# station_meteo.net
KiCad netlist of a schematic drawn in EasyEDA Pro
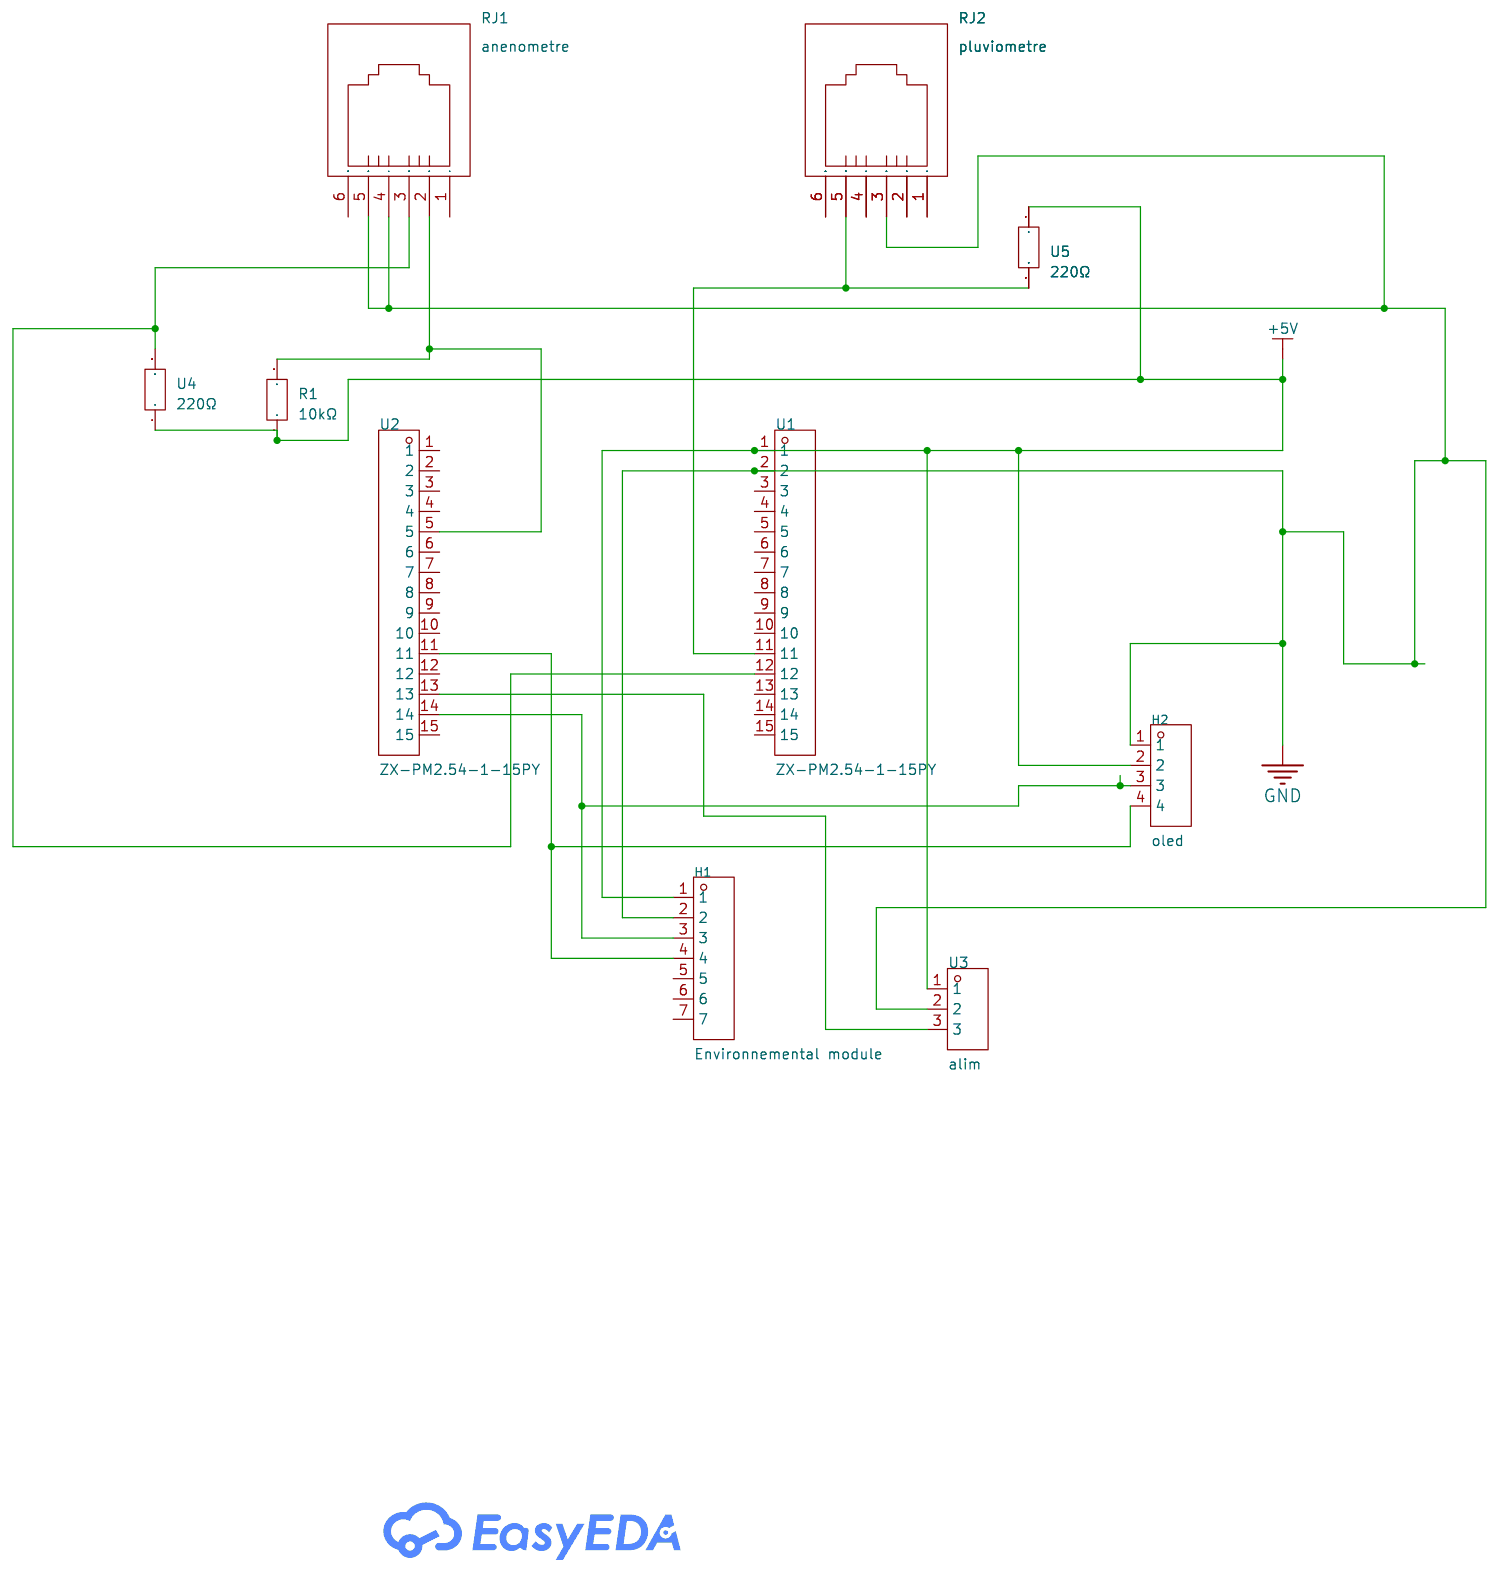
[diagram p0: schematic sheet]

(export (version "E")
  (design (tool "Eeschema 10.0.6"))
  (components
    (comp (ref "H1")
      (value "Environnemental module")
      (footprint "easyedapro:HDR-TH_7P-P2.54-V-F")
      (fields (field (name "Manufacturer") "XFCN(兴飞)"))
      (libsource (lib "easyedapro") (part "PM254V-11-07-H85"))
    )
    (comp (ref "H2")
      (value "oled")
      (footprint "easyedapro:HDR-TH_4P-P2.54-V-F")
      (fields (field (name "Manufacturer") "BOOMELE(博穆精密)"))
      (libsource (lib "easyedapro") (part "2.54-1*4P母"))
    )
    (comp (ref "R1")
      (value "10kΩ")
      (footprint "easyedapro:RES-TH_BD2.7-L6.2-P10.20-D0.4")
      (fields (field (name "Manufacturer Part") "MF1/4W-10K±1%-ST52") (field (name "Manufacturer") "VO(翔胜)"))
      (libsource (lib "easyedapro") (part "MF1/4W-10K±1%-ST52"))
    )
    (comp (ref "RJ1")
      (value "anenometre")
      (footprint "easyedapro:RJ11-TH_DS1133-S60BPX")
      (description "Connector Type:RJ12 Jack Number of Ports:1 LED:- Shielding:- Ratings:-")
      (fields (field (name "Manufacturer") "CONNFLY"))
      (libsource (lib "easyedapro") (part "DS1133-S60BPX"))
    )
    (comp (ref "RJ2")
      (value "pluviometre")
      (footprint "easyedapro:RJ11-TH_DS1133-S60BPX")
      (description "Connector Type:RJ12 Jack Number of Ports:1 LED:- Shielding:- Ratings:-")
      (fields (field (name "Manufacturer") "CONNFLY"))
      (libsource (lib "easyedapro") (part "DS1133-S60BPX"))
    )
    (comp (ref "U1")
      (value "ZX-PM2.54-1-15PY")
      (footprint "easyedapro:HDR-TH_15P-P2.54-V-F")
      (fields (field (name "Manufacturer") "Megastar(兆星)"))
      (libsource (lib "easyedapro") (part "ZX-PM2.54-1-15PY"))
    )
    (comp (ref "U2")
      (value "ZX-PM2.54-1-15PY")
      (footprint "easyedapro:HDR-TH_15P-P2.54-V-F")
      (fields (field (name "Manufacturer") "Megastar(兆星)"))
      (libsource (lib "easyedapro") (part "ZX-PM2.54-1-15PY"))
    )
    (comp (ref "U3")
      (value "alim")
      (footprint "easyedapro:CONN-TH_3P-P5.08_DB128L-5.08-3P-BK-S")
      (fields (field (name "Manufacturer") "DORABO(地博电气)"))
      (libsource (lib "easyedapro") (part "DB128L-5.08-3P-BK-S"))
    )
    (comp (ref "U4")
      (value "220Ω")
      (footprint "easyedapro:RES-TH_BD2.4-L6.3-P10.30-D0.6")
      (fields (field (name "Manufacturer Part") "MFR-25FBF52-220R") (field (name "Manufacturer") "YAGEO(国巨)"))
      (libsource (lib "easyedapro") (part "MFR-25FBF52-220R"))
    )
    (comp (ref "U5")
      (value "220Ω")
      (footprint "easyedapro:RES-TH_BD2.4-L6.3-P10.30-D0.6")
      (fields (field (name "Manufacturer Part") "MFR-25FBF52-220R") (field (name "Manufacturer") "YAGEO(国巨)"))
      (libsource (lib "easyedapro") (part "MFR-25FBF52-220R"))
    )
  )
  (nets
    (net (code "1") (name "+5V") (class "Default")
      (node (ref "H1") (pin "1") (pinfunction "1_1") (pintype "input"))
      (node (ref "H2") (pin "2") (pinfunction "2_2") (pintype "input"))
      (node (ref "R1") (pin "1") (pinfunction "1_1") (pintype "unspecified"))
      (node (ref "U1") (pin "1") (pinfunction "1_1") (pintype "unspecified"))
      (node (ref "U3") (pin "1") (pinfunction "1_1") (pintype "unspecified"))
      (node (ref "U4") (pin "1") (pinfunction "1_1") (pintype "unspecified"))
      (node (ref "U5") (pin "1") (pinfunction "1_1") (pintype "unspecified"))
    )
    (net (code "2") (name "GND") (class "Default")
      (node (ref "H1") (pin "2") (pinfunction "2_2") (pintype "input"))
      (node (ref "H2") (pin "1") (pinfunction "1_1") (pintype "input"))
      (node (ref "RJ1") (pin "4") (pinfunction "4_4") (pintype "unspecified"))
      (node (ref "RJ1") (pin "5") (pinfunction "5_5") (pintype "unspecified"))
      (node (ref "RJ2") (pin "3") (pinfunction "3_3") (pintype "unspecified"))
      (node (ref "U1") (pin "2") (pinfunction "2_2") (pintype "unspecified"))
      (node (ref "U3") (pin "2") (pinfunction "2_2") (pintype "unspecified"))
    )
    (net (code "3") (name "Net-(H1-Pad3)") (class "Default")
      (node (ref "H1") (pin "3") (pinfunction "3_3") (pintype "input"))
      (node (ref "H2") (pin "3") (pinfunction "3_3") (pintype "input"))
      (node (ref "U2") (pin "14") (pinfunction "14_14") (pintype "unspecified"))
    )
    (net (code "4") (name "Net-(H1-Pad4)") (class "Default")
      (node (ref "H1") (pin "4") (pinfunction "4_4") (pintype "input"))
      (node (ref "H2") (pin "4") (pinfunction "4_4") (pintype "input"))
      (node (ref "U2") (pin "11") (pinfunction "11_11") (pintype "unspecified"))
    )
    (net (code "5") (name "Net-(R1-Pad2)") (class "Default")
      (node (ref "R1") (pin "2") (pinfunction "2_2") (pintype "unspecified"))
      (node (ref "RJ1") (pin "2") (pinfunction "2_2") (pintype "unspecified"))
      (node (ref "U2") (pin "5") (pinfunction "5_5") (pintype "unspecified"))
    )
    (net (code "6") (name "Net-(RJ1-Pad3)") (class "Default")
      (node (ref "RJ1") (pin "3") (pinfunction "3_3") (pintype "unspecified"))
      (node (ref "U1") (pin "12") (pinfunction "12_12") (pintype "unspecified"))
      (node (ref "U4") (pin "2") (pinfunction "2_2") (pintype "unspecified"))
    )
    (net (code "7") (name "Net-(RJ2-Pad5)") (class "Default")
      (node (ref "RJ2") (pin "5") (pinfunction "5_5") (pintype "unspecified"))
      (node (ref "U1") (pin "11") (pinfunction "11_11") (pintype "unspecified"))
      (node (ref "U5") (pin "2") (pinfunction "2_2") (pintype "unspecified"))
    )
    (net (code "8") (name "Net-(U2-Pad13)") (class "Default")
      (node (ref "U2") (pin "13") (pinfunction "13_13") (pintype "unspecified"))
      (node (ref "U3") (pin "3") (pinfunction "3_3") (pintype "unspecified"))
    )
    (net (code "9") (name "unconnected-(H1-Pad5)") (class "Default")
      (node (ref "H1") (pin "5") (pinfunction "5_5") (pintype "input"))
    )
    (net (code "10") (name "unconnected-(H1-Pad6)") (class "Default")
      (node (ref "H1") (pin "6") (pinfunction "6_6") (pintype "input"))
    )
    (net (code "11") (name "unconnected-(H1-Pad7)") (class "Default")
      (node (ref "H1") (pin "7") (pinfunction "7_7") (pintype "input"))
    )
    (net (code "12") (name "unconnected-(RJ1-Pad1)") (class "Default")
      (node (ref "RJ1") (pin "1") (pinfunction "1_1") (pintype "unspecified"))
    )
    (net (code "13") (name "unconnected-(RJ1-Pad6)") (class "Default")
      (node (ref "RJ1") (pin "6") (pinfunction "6_6") (pintype "unspecified"))
    )
    (net (code "14") (name "unconnected-(RJ2-Pad1)") (class "Default")
      (node (ref "RJ2") (pin "1") (pinfunction "1_1") (pintype "unspecified"))
    )
    (net (code "15") (name "unconnected-(RJ2-Pad2)") (class "Default")
      (node (ref "RJ2") (pin "2") (pinfunction "2_2") (pintype "unspecified"))
    )
    (net (code "16") (name "unconnected-(RJ2-Pad4)") (class "Default")
      (node (ref "RJ2") (pin "4") (pinfunction "4_4") (pintype "unspecified"))
    )
    (net (code "17") (name "unconnected-(RJ2-Pad6)") (class "Default")
      (node (ref "RJ2") (pin "6") (pinfunction "6_6") (pintype "unspecified"))
    )
    (net (code "18") (name "unconnected-(U1-Pad3)") (class "Default")
      (node (ref "U1") (pin "3") (pinfunction "3_3") (pintype "unspecified"))
    )
    (net (code "19") (name "unconnected-(U1-Pad4)") (class "Default")
      (node (ref "U1") (pin "4") (pinfunction "4_4") (pintype "unspecified"))
    )
    (net (code "20") (name "unconnected-(U1-Pad5)") (class "Default")
      (node (ref "U1") (pin "5") (pinfunction "5_5") (pintype "unspecified"))
    )
    (net (code "21") (name "unconnected-(U1-Pad6)") (class "Default")
      (node (ref "U1") (pin "6") (pinfunction "6_6") (pintype "unspecified"))
    )
    (net (code "22") (name "unconnected-(U1-Pad7)") (class "Default")
      (node (ref "U1") (pin "7") (pinfunction "7_7") (pintype "unspecified"))
    )
    (net (code "23") (name "unconnected-(U1-Pad8)") (class "Default")
      (node (ref "U1") (pin "8") (pinfunction "8_8") (pintype "unspecified"))
    )
    (net (code "24") (name "unconnected-(U1-Pad9)") (class "Default")
      (node (ref "U1") (pin "9") (pinfunction "9_9") (pintype "unspecified"))
    )
    (net (code "25") (name "unconnected-(U1-Pad10)") (class "Default")
      (node (ref "U1") (pin "10") (pinfunction "10_10") (pintype "unspecified"))
    )
    (net (code "26") (name "unconnected-(U1-Pad13)") (class "Default")
      (node (ref "U1") (pin "13") (pinfunction "13_13") (pintype "unspecified"))
    )
    (net (code "27") (name "unconnected-(U1-Pad14)") (class "Default")
      (node (ref "U1") (pin "14") (pinfunction "14_14") (pintype "unspecified"))
    )
    (net (code "28") (name "unconnected-(U1-Pad15)") (class "Default")
      (node (ref "U1") (pin "15") (pinfunction "15_15") (pintype "unspecified"))
    )
    (net (code "29") (name "unconnected-(U2-Pad1)") (class "Default")
      (node (ref "U2") (pin "1") (pinfunction "1_1") (pintype "unspecified"))
    )
    (net (code "30") (name "unconnected-(U2-Pad2)") (class "Default")
      (node (ref "U2") (pin "2") (pinfunction "2_2") (pintype "unspecified"))
    )
    (net (code "31") (name "unconnected-(U2-Pad3)") (class "Default")
      (node (ref "U2") (pin "3") (pinfunction "3_3") (pintype "unspecified"))
    )
    (net (code "32") (name "unconnected-(U2-Pad4)") (class "Default")
      (node (ref "U2") (pin "4") (pinfunction "4_4") (pintype "unspecified"))
    )
    (net (code "33") (name "unconnected-(U2-Pad6)") (class "Default")
      (node (ref "U2") (pin "6") (pinfunction "6_6") (pintype "unspecified"))
    )
    (net (code "34") (name "unconnected-(U2-Pad7)") (class "Default")
      (node (ref "U2") (pin "7") (pinfunction "7_7") (pintype "unspecified"))
    )
    (net (code "35") (name "unconnected-(U2-Pad8)") (class "Default")
      (node (ref "U2") (pin "8") (pinfunction "8_8") (pintype "unspecified"))
    )
    (net (code "36") (name "unconnected-(U2-Pad9)") (class "Default")
      (node (ref "U2") (pin "9") (pinfunction "9_9") (pintype "unspecified"))
    )
    (net (code "37") (name "unconnected-(U2-Pad10)") (class "Default")
      (node (ref "U2") (pin "10") (pinfunction "10_10") (pintype "unspecified"))
    )
    (net (code "38") (name "unconnected-(U2-Pad12)") (class "Default")
      (node (ref "U2") (pin "12") (pinfunction "12_12") (pintype "unspecified"))
    )
    (net (code "39") (name "unconnected-(U2-Pad15)") (class "Default")
      (node (ref "U2") (pin "15") (pinfunction "15_15") (pintype "unspecified"))
    )
  )
)
